# SmartCitizen_DVK.net
KiCad netlist of a schematic drawn in EAGLE
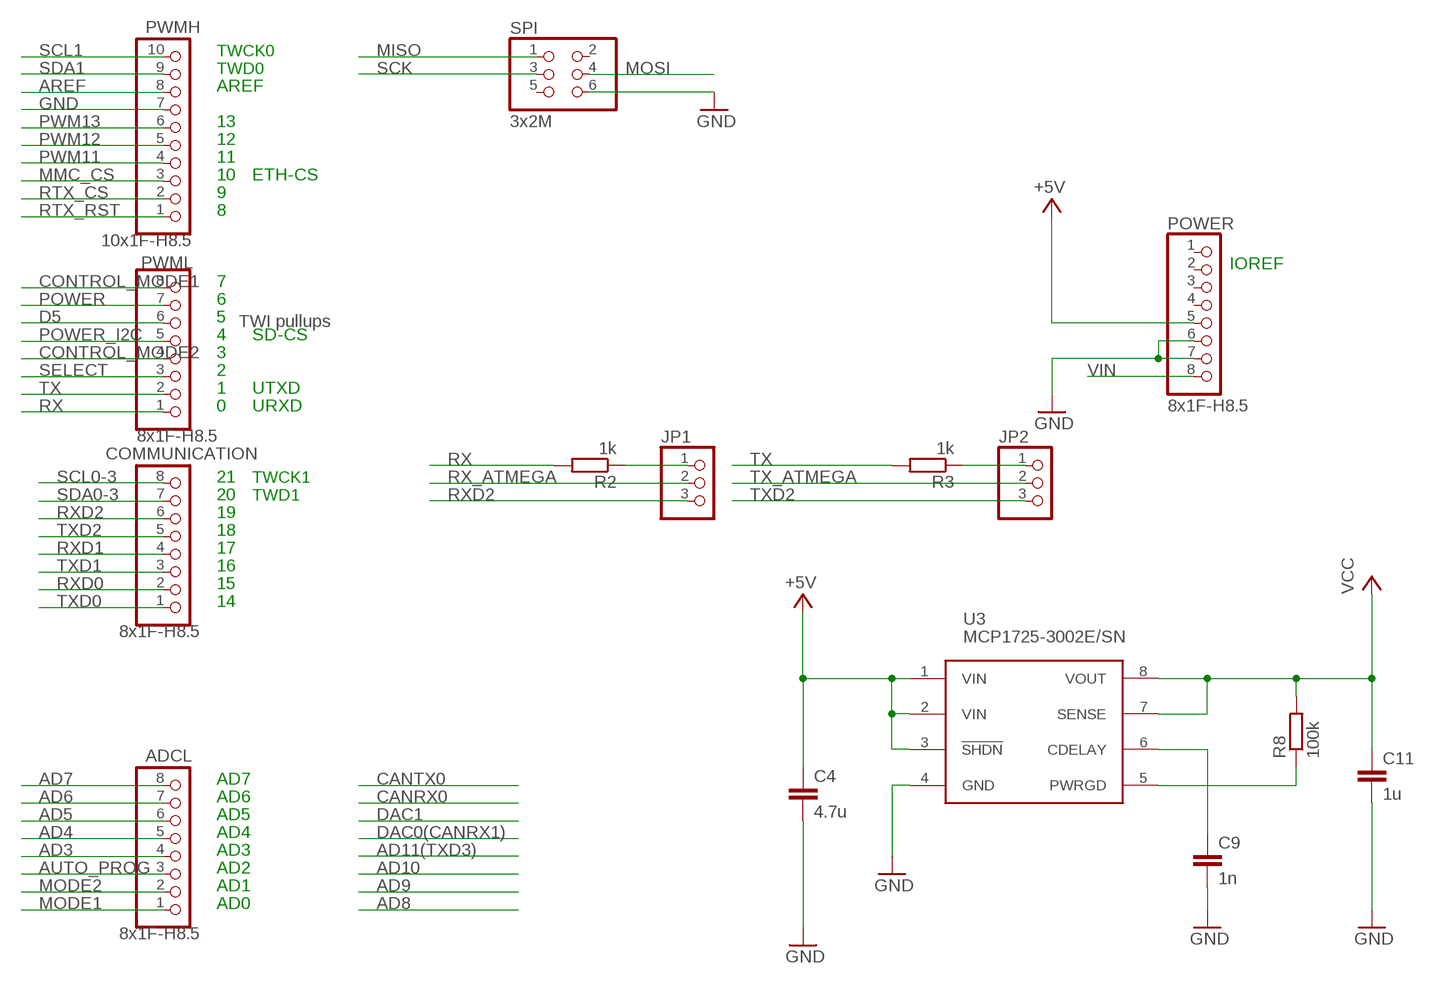
[diagram p0: schematic, sheet 1]
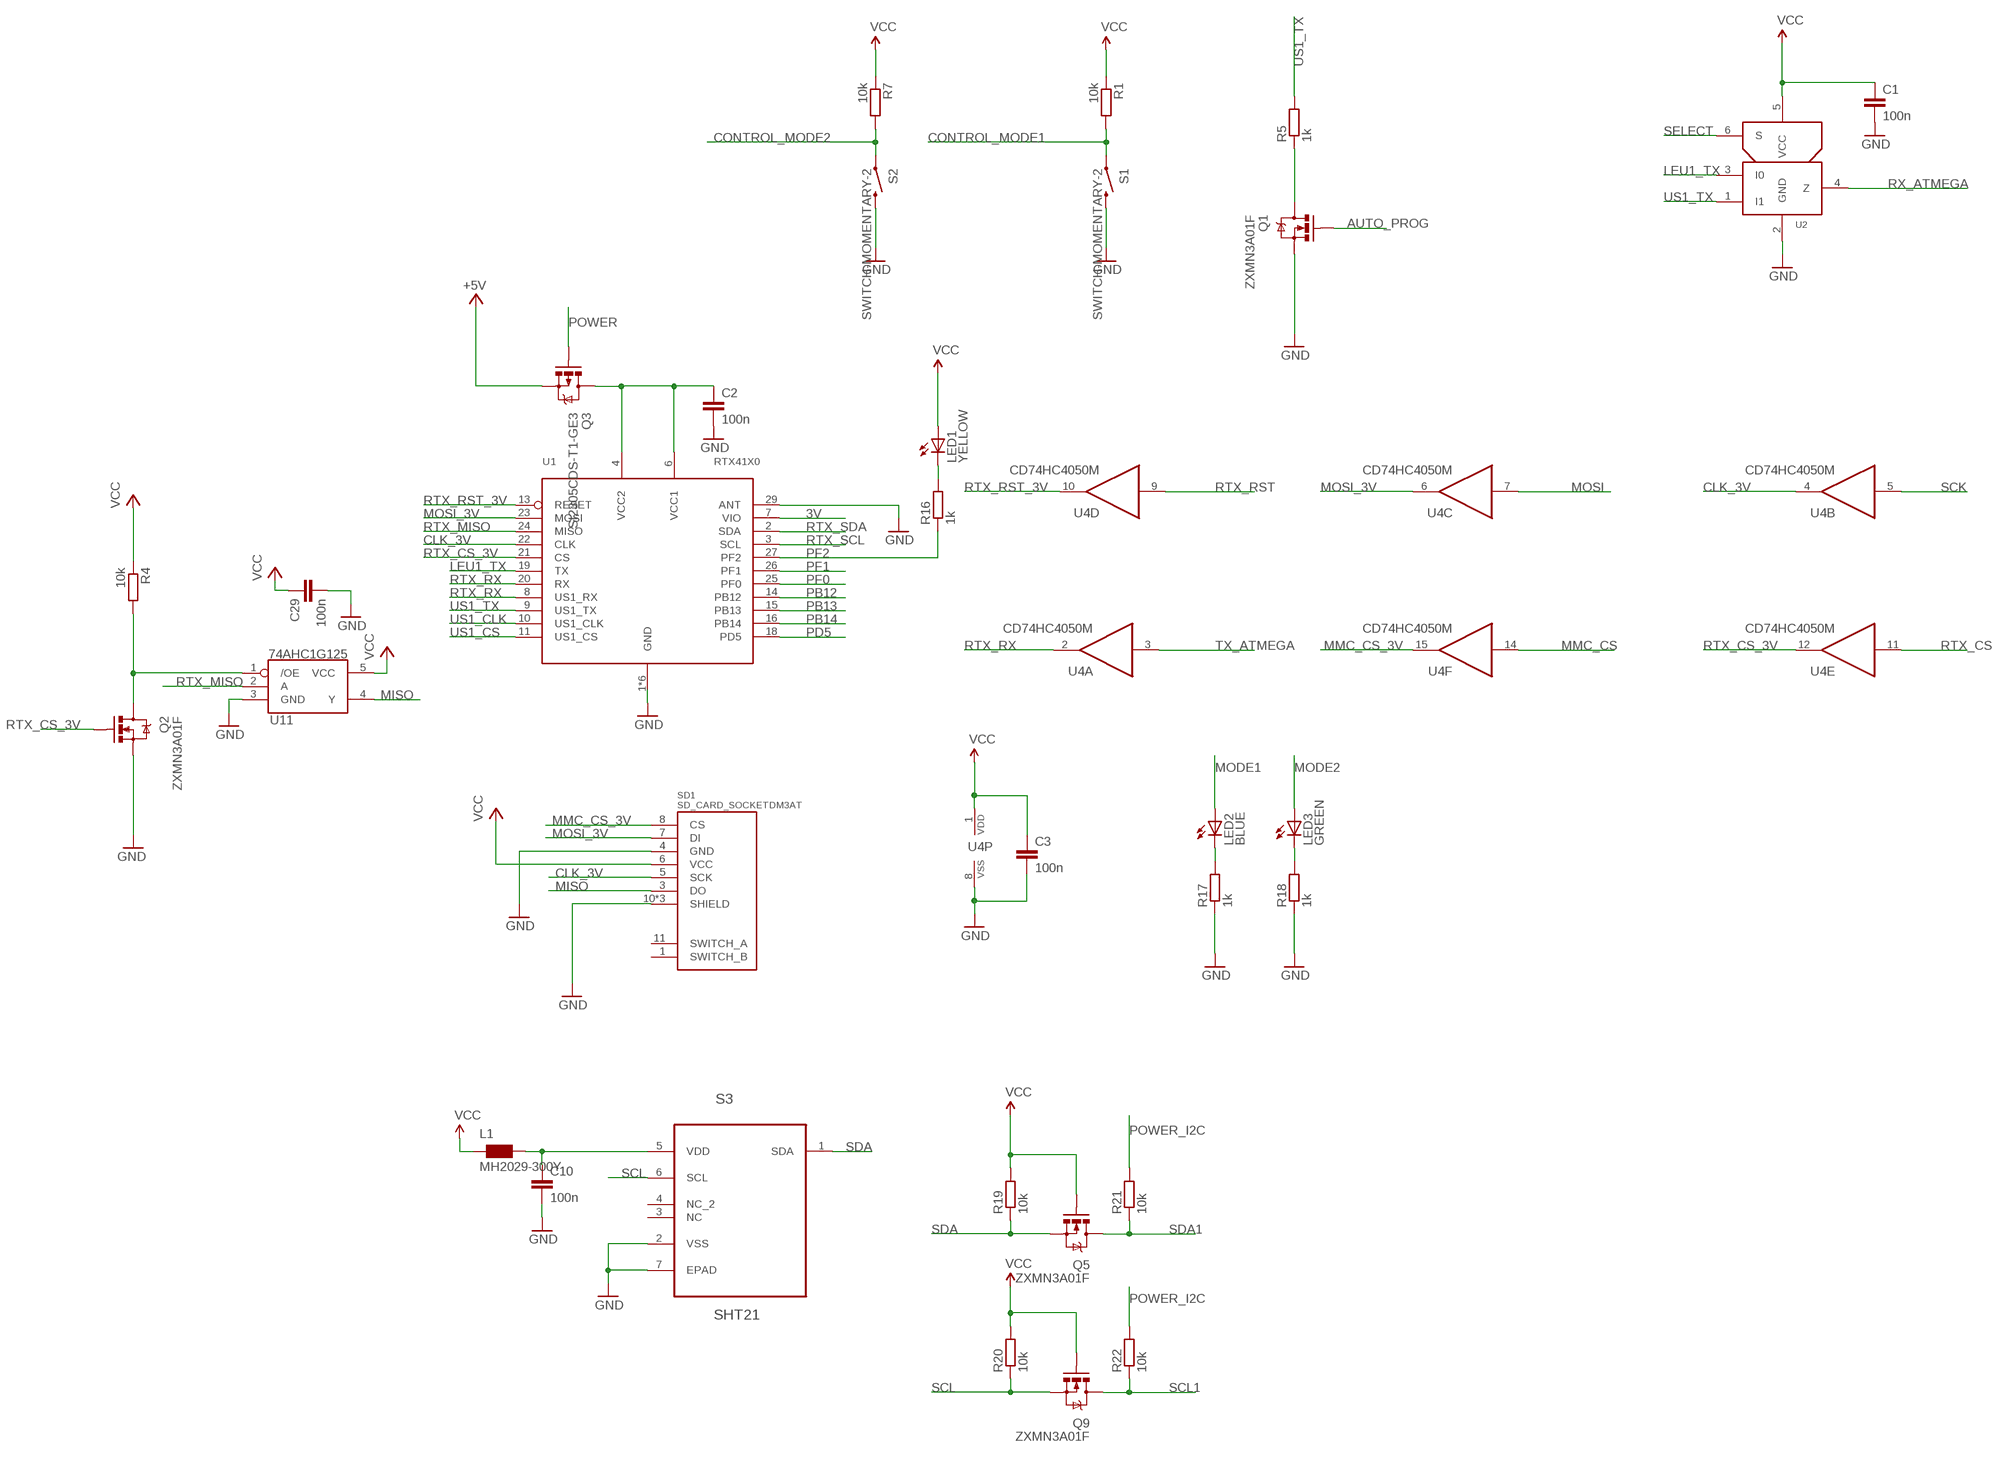
[diagram p1: schematic, sheet 2]

(export (version "E")
  (design (tool "Eeschema 10.0.6"))
  (components
    (comp (ref "C1")
      (value "100n")
      (footprint "eagle-import:C0805")
      (libsource (lib "eagle-import") (part "C-EUC0805"))
    )
    (comp (ref "C2")
      (value "100n")
      (footprint "eagle-import:C0805")
      (libsource (lib "eagle-import") (part "C-EUC0805"))
    )
    (comp (ref "C3")
      (value "100n")
      (footprint "eagle-import:C0805")
      (libsource (lib "eagle-import") (part "C-EUC0805"))
    )
    (comp (ref "C10")
      (value "100n")
      (footprint "eagle-import:C0805")
      (libsource (lib "eagle-import") (part "rcl_C-EUC0805"))
    )
    (comp (ref "C29")
      (value "100n")
      (footprint "eagle-import:C0805")
      (libsource (lib "eagle-import") (part "rcl_C-EUC0805"))
    )
    (comp (ref "L1")
      (value "MH2029-300Y")
      (footprint "eagle-import:0805")
      (libsource (lib "eagle-import") (part "WE-CBF_0805"))
    )
    (comp (ref "LED1")
      (value "YELLOW")
      (footprint "eagle-import:CHIPLED_0805")
      (libsource (lib "eagle-import") (part "LEDCHIPLED_0805"))
    )
    (comp (ref "LED2")
      (value "BLUE")
      (footprint "eagle-import:CHIPLED_0805")
      (libsource (lib "eagle-import") (part "LEDCHIPLED_0805"))
    )
    (comp (ref "LED3")
      (value "GREEN")
      (footprint "eagle-import:CHIPLED_0805")
      (libsource (lib "eagle-import") (part "LEDCHIPLED_0805"))
    )
    (comp (ref "Q1")
      (value "ZXMN3A01F")
      (footprint "eagle-import:SOT23")
      (libsource (lib "eagle-import") (part "MOSFET-NCHANNELBSS123LT1G"))
    )
    (comp (ref "Q2")
      (value "ZXMN3A01F")
      (footprint "eagle-import:SOT23")
      (libsource (lib "eagle-import") (part "MOSFET-NCHANNELBSS123LT1G"))
    )
    (comp (ref "Q3")
      (value "SI2305CDS-T1-GE3")
      (footprint "eagle-import:SOT23-3")
      (libsource (lib "eagle-import") (part "MOSFET-PCHANNEL"))
    )
    (comp (ref "Q5")
      (value "ZXMN3A01F")
      (footprint "eagle-import:SOT23")
      (libsource (lib "eagle-import") (part "MOSFET-NCHANNELBSS123LT1G"))
    )
    (comp (ref "Q9")
      (value "ZXMN3A01F")
      (footprint "eagle-import:SOT23")
      (libsource (lib "eagle-import") (part "MOSFET-NCHANNELBSS123LT1G"))
    )
    (comp (ref "R1")
      (value "10k")
      (footprint "eagle-import:R0805")
      (libsource (lib "eagle-import") (part "R-EU_R0805"))
    )
    (comp (ref "R4")
      (value "10k")
      (footprint "eagle-import:R0805")
      (libsource (lib "eagle-import") (part "R-EU_R0805"))
    )
    (comp (ref "R5")
      (value "1k")
      (footprint "eagle-import:R0805")
      (libsource (lib "eagle-import") (part "R-EU_R0805"))
    )
    (comp (ref "R7")
      (value "10k")
      (footprint "eagle-import:R0805")
      (libsource (lib "eagle-import") (part "R-EU_R0805"))
    )
    (comp (ref "R16")
      (value "1k")
      (footprint "eagle-import:R0805")
      (libsource (lib "eagle-import") (part "R-EU_R0805"))
    )
    (comp (ref "R17")
      (value "1k")
      (footprint "eagle-import:R0805")
      (libsource (lib "eagle-import") (part "R-EU_R0805"))
    )
    (comp (ref "R18")
      (value "1k")
      (footprint "eagle-import:R0805")
      (libsource (lib "eagle-import") (part "R-EU_R0805"))
    )
    (comp (ref "R19")
      (value "10k")
      (footprint "eagle-import:R0805")
      (libsource (lib "eagle-import") (part "R-EU_R0805"))
    )
    (comp (ref "R20")
      (value "10k")
      (footprint "eagle-import:R0805")
      (libsource (lib "eagle-import") (part "R-EU_R0805"))
    )
    (comp (ref "R21")
      (value "10k")
      (footprint "eagle-import:R0805")
      (libsource (lib "eagle-import") (part "R-EU_R0805"))
    )
    (comp (ref "R22")
      (value "10k")
      (footprint "eagle-import:R0805")
      (libsource (lib "eagle-import") (part "R-EU_R0805"))
    )
    (comp (ref "S1")
      (value "SWITCH-MOMENTARY-2")
      (footprint "eagle-import:TACTILE_SWITCH_TALL")
      (libsource (lib "eagle-import") (part "SWITCH-MOMENTARY-2"))
    )
    (comp (ref "S2")
      (value "SWITCH-MOMENTARY-2")
      (footprint "eagle-import:TACTILE_SWITCH_TALL")
      (libsource (lib "eagle-import") (part "SWITCH-MOMENTARY-2"))
    )
    (comp (ref "S3")
      (value "SHT21")
      (footprint "eagle-import:DFN300X300X110-7N")
      (libsource (lib "eagle-import") (part "SHT21"))
    )
    (comp (ref "SD1")
      (value "SD_CARD_SOCKETDM3AT")
      (footprint "eagle-import:DM3AT")
      (libsource (lib "eagle-import") (part "SD_CARD_SOCKETDM3AT"))
    )
    (comp (ref "U1")
      (value "RTX41X0")
      (footprint "eagle-import:RTX41X0")
      (libsource (lib "eagle-import") (part "RTX41X0"))
    )
    (comp (ref "U2")
      (value "NC7SZ157P6X")
      (footprint "eagle-import:SC70")
      (libsource (lib "eagle-import") (part "NC7SV157"))
    )
    (comp (ref "U4")
      (value "CD74HC4050M")
      (footprint "eagle-import:SO16")
      (libsource (lib "eagle-import") (part "4050D"))
    )
    (comp (ref "U11")
      (value "74AHC1G125")
      (footprint "eagle-import:SOT23-5")
      (libsource (lib "eagle-import") (part "74AHC1G125"))
    )
    (comp (ref "ADCL")
      (value "8x1F-H8.5")
      (footprint "eagle-import:1X08")
      (libsource (lib "eagle-import") (part "PINHD-1X8"))
    )
    (comp (ref "C4")
      (value "4.7u")
      (footprint "eagle-import:C0805")
      (libsource (lib "eagle-import") (part "rcl_C-EUC0805"))
    )
    (comp (ref "C9")
      (value "1n")
      (footprint "eagle-import:C0805")
      (libsource (lib "eagle-import") (part "rcl_C-EUC0805"))
    )
    (comp (ref "C11")
      (value "1u")
      (footprint "eagle-import:C0805")
      (libsource (lib "eagle-import") (part "rcl_C-EUC0805"))
    )
    (comp (ref "COMMUNICATION")
      (value "8x1F-H8.5")
      (footprint "eagle-import:1X08")
      (libsource (lib "eagle-import") (part "PINHD-1X8"))
    )
    (comp (ref "JP1")
      (value "PINHD-1X3")
      (footprint "eagle-import:1X03")
      (libsource (lib "eagle-import") (part "PINHD-1X3"))
    )
    (comp (ref "JP2")
      (value "PINHD-1X3")
      (footprint "eagle-import:1X03")
      (libsource (lib "eagle-import") (part "PINHD-1X3"))
    )
    (comp (ref "POWER")
      (value "8x1F-H8.5")
      (footprint "eagle-import:1X08")
      (libsource (lib "eagle-import") (part "PINHD-1X8"))
    )
    (comp (ref "PWMH")
      (value "10x1F-H8.5")
      (footprint "eagle-import:1X10")
      (libsource (lib "eagle-import") (part "PINHD-1X10"))
    )
    (comp (ref "PWML")
      (value "8x1F-H8.5")
      (footprint "eagle-import:1X08")
      (libsource (lib "eagle-import") (part "PINHD-1X8"))
    )
    (comp (ref "R2")
      (value "1k")
      (footprint "eagle-import:R0805")
      (libsource (lib "eagle-import") (part "R-EU_R0805"))
    )
    (comp (ref "R3")
      (value "1k")
      (footprint "eagle-import:R0805")
      (libsource (lib "eagle-import") (part "R-EU_R0805"))
    )
    (comp (ref "R8")
      (value "100k")
      (footprint "eagle-import:R0805")
      (libsource (lib "eagle-import") (part "R-EU_R0805"))
    )
    (comp (ref "SPI")
      (value "3x2M")
      (footprint "eagle-import:2X03")
      (libsource (lib "eagle-import") (part "PINHD-2X3"))
    )
    (comp (ref "U3")
      (value "MCP1725-3002E/SN")
      (footprint "eagle-import:SOIC8")
      (libsource (lib "eagle-import") (part "MCP1725"))
    )
  )
  (nets
    (net (code "1") (name "+5V") (class "Default")
      (node (ref "C4") (pin "1") (pinfunction "1_1") (pintype "passive"))
      (node (ref "POWER") (pin "5") (pinfunction "5_5") (pintype "passive"))
      (node (ref "Q3") (pin "2") (pinfunction "S_2") (pintype "passive"))
      (node (ref "U3") (pin "1") (pinfunction "VIN_1") (pintype "bidirectional"))
      (node (ref "U3") (pin "2") (pinfunction "VIN_2") (pintype "bidirectional"))
      (node (ref "U3") (pin "3") (pinfunction "~{SHDN}_3") (pintype "bidirectional"))
    )
    (net (code "2") (name "3V") (class "Default")
      (node (ref "U1") (pin "7") (pinfunction "VIO_7") (pintype "bidirectional"))
    )
    (net (code "3") (name "AD3") (class "Default")
      (node (ref "ADCL") (pin "4") (pinfunction "4_4") (pintype "passive"))
    )
    (net (code "4") (name "AD4") (class "Default")
      (node (ref "ADCL") (pin "5") (pinfunction "5_5") (pintype "passive"))
    )
    (net (code "5") (name "AD5") (class "Default")
      (node (ref "ADCL") (pin "6") (pinfunction "6_6") (pintype "passive"))
    )
    (net (code "6") (name "AD6") (class "Default")
      (node (ref "ADCL") (pin "7") (pinfunction "7_7") (pintype "passive"))
    )
    (net (code "7") (name "AD7") (class "Default")
      (node (ref "ADCL") (pin "8") (pinfunction "8_8") (pintype "passive"))
    )
    (net (code "12") (name "AREF") (class "Default")
      (node (ref "PWMH") (pin "8") (pinfunction "8_8") (pintype "passive"))
    )
    (net (code "13") (name "AUTO_PROG") (class "Default")
      (node (ref "ADCL") (pin "3") (pinfunction "3_3") (pintype "passive"))
      (node (ref "Q1") (pin "1") (pinfunction "G_1") (pintype "passive"))
    )
    (net (code "16") (name "CLK_3V") (class "Default")
      (node (ref "SD1") (pin "5") (pinfunction "SCK_5") (pintype "bidirectional"))
      (node (ref "U1") (pin "22") (pinfunction "CLK_22") (pintype "bidirectional"))
      (node (ref "U4") (pin "4") (pinfunction "O_4") (pintype "output"))
    )
    (net (code "17") (name "CONTROL_MODE1") (class "Default")
      (node (ref "PWML") (pin "8") (pinfunction "8_8") (pintype "passive"))
      (node (ref "R1") (pin "2") (pinfunction "2_2") (pintype "passive"))
      (node (ref "S1") (pin "A2") (pinfunction "1_A2") (pintype "passive"))
    )
    (net (code "18") (name "CONTROL_MODE2") (class "Default")
      (node (ref "PWML") (pin "4") (pinfunction "4_4") (pintype "passive"))
      (node (ref "R7") (pin "2") (pinfunction "2_2") (pintype "passive"))
      (node (ref "S2") (pin "A2") (pinfunction "1_A2") (pintype "passive"))
    )
    (net (code "19") (name "D5") (class "Default")
      (node (ref "PWML") (pin "6") (pinfunction "6_6") (pintype "passive"))
    )
    (net (code "22") (name "GND") (class "Default")
      (node (ref "C1") (pin "2") (pinfunction "2_2") (pintype "passive"))
      (node (ref "C10") (pin "2") (pinfunction "2_2") (pintype "passive"))
      (node (ref "C11") (pin "2") (pinfunction "2_2") (pintype "passive"))
      (node (ref "C2") (pin "2") (pinfunction "2_2") (pintype "passive"))
      (node (ref "C29") (pin "2") (pinfunction "2_2") (pintype "passive"))
      (node (ref "C3") (pin "2") (pinfunction "2_2") (pintype "passive"))
      (node (ref "C4") (pin "2") (pinfunction "2_2") (pintype "passive"))
      (node (ref "C9") (pin "2") (pinfunction "2_2") (pintype "passive"))
      (node (ref "POWER") (pin "6") (pinfunction "6_6") (pintype "passive"))
      (node (ref "POWER") (pin "7") (pinfunction "7_7") (pintype "passive"))
      (node (ref "PWMH") (pin "7") (pinfunction "7_7") (pintype "passive"))
      (node (ref "Q1") (pin "2") (pinfunction "S_2") (pintype "passive"))
      (node (ref "Q2") (pin "2") (pinfunction "S_2") (pintype "passive"))
      (node (ref "R17") (pin "1") (pinfunction "1_1") (pintype "passive"))
      (node (ref "R18") (pin "1") (pinfunction "1_1") (pintype "passive"))
      (node (ref "S1") (pin "B2") (pinfunction "2_B2") (pintype "passive"))
      (node (ref "S2") (pin "B2") (pinfunction "2_B2") (pintype "passive"))
      (node (ref "S3") (pin "2") (pinfunction "VSS_2") (pintype "power_in"))
      (node (ref "S3") (pin "7") (pinfunction "EPAD_7") (pintype "passive"))
      (node (ref "SD1") (pin "10") (pinfunction "SHIELD_10") (pintype "bidirectional"))
      (node (ref "SD1") (pin "12") (pinfunction "SHIELD_12") (pintype "bidirectional"))
      (node (ref "SD1") (pin "13") (pinfunction "SHIELD_13") (pintype "bidirectional"))
      (node (ref "SD1") (pin "4") (pinfunction "GND_4") (pintype "bidirectional"))
      (node (ref "SPI") (pin "6") (pinfunction "6_6") (pintype "passive"))
      (node (ref "U1") (pin "1") (pinfunction "GND_1") (pintype "power_in"))
      (node (ref "U1") (pin "12") (pinfunction "GND_12") (pintype "power_in"))
      (node (ref "U1") (pin "17") (pinfunction "GND_17") (pintype "power_in"))
      (node (ref "U1") (pin "28") (pinfunction "GND_28") (pintype "power_in"))
      (node (ref "U1") (pin "29") (pinfunction "ANT_29") (pintype "bidirectional"))
      (node (ref "U1") (pin "30") (pinfunction "GND_30") (pintype "power_in"))
      (node (ref "U1") (pin "5") (pinfunction "GND_5") (pintype "power_in"))
      (node (ref "U11") (pin "3") (pinfunction "GND_3") (pintype "bidirectional"))
      (node (ref "U2") (pin "2") (pinfunction "GND_2") (pintype "bidirectional"))
      (node (ref "U3") (pin "4") (pinfunction "GND_4") (pintype "bidirectional"))
      (node (ref "U4") (pin "8") (pinfunction "VSS_8") (pintype "power_in"))
    )
    (net (code "23") (name "LEU1_TX") (class "Default")
      (node (ref "U1") (pin "19") (pinfunction "TX_19") (pintype "bidirectional"))
      (node (ref "U2") (pin "3") (pinfunction "I0_3") (pintype "bidirectional"))
    )
    (net (code "24") (name "MISO") (class "Default")
      (node (ref "SD1") (pin "3") (pinfunction "DO_3") (pintype "bidirectional"))
      (node (ref "SPI") (pin "1") (pinfunction "1_1") (pintype "passive"))
      (node (ref "U11") (pin "4") (pinfunction "Y_4") (pintype "bidirectional"))
    )
    (net (code "25") (name "MMC_CS") (class "Default")
      (node (ref "PWMH") (pin "3") (pinfunction "3_3") (pintype "passive"))
      (node (ref "U4") (pin "14") (pinfunction "I_14") (pintype "input"))
    )
    (net (code "26") (name "MMC_CS_3V") (class "Default")
      (node (ref "SD1") (pin "8") (pinfunction "CS_8") (pintype "bidirectional"))
      (node (ref "U4") (pin "15") (pinfunction "O_15") (pintype "output"))
    )
    (net (code "27") (name "MODE1") (class "Default")
      (node (ref "ADCL") (pin "1") (pinfunction "1_1") (pintype "passive"))
      (node (ref "LED2") (pin "A") (pinfunction "A_A") (pintype "passive"))
    )
    (net (code "28") (name "MODE2") (class "Default")
      (node (ref "ADCL") (pin "2") (pinfunction "2_2") (pintype "passive"))
      (node (ref "LED3") (pin "A") (pinfunction "A_A") (pintype "passive"))
    )
    (net (code "29") (name "MOSI") (class "Default")
      (node (ref "SPI") (pin "4") (pinfunction "4_4") (pintype "passive"))
      (node (ref "U4") (pin "7") (pinfunction "I_7") (pintype "input"))
    )
    (net (code "30") (name "MOSI_3V") (class "Default")
      (node (ref "SD1") (pin "7") (pinfunction "DI_7") (pintype "bidirectional"))
      (node (ref "U1") (pin "23") (pinfunction "MOSI_23") (pintype "bidirectional"))
      (node (ref "U4") (pin "6") (pinfunction "O_6") (pintype "output"))
    )
    (net (code "31") (name "Net-(JP1-Pad1)") (class "Default")
      (node (ref "JP1") (pin "1") (pinfunction "1_1") (pintype "passive"))
      (node (ref "R2") (pin "1") (pinfunction "1_1") (pintype "passive"))
    )
    (net (code "32") (name "Net-(JP2-Pad1)") (class "Default")
      (node (ref "JP2") (pin "1") (pinfunction "1_1") (pintype "passive"))
      (node (ref "R3") (pin "1") (pinfunction "1_1") (pintype "passive"))
    )
    (net (code "33") (name "Net-(LED1-PadC)") (class "Default")
      (node (ref "LED1") (pin "C") (pinfunction "C_C") (pintype "passive"))
      (node (ref "R16") (pin "2") (pinfunction "2_2") (pintype "passive"))
    )
    (net (code "34") (name "Net-(LED2-PadC)") (class "Default")
      (node (ref "LED2") (pin "C") (pinfunction "C_C") (pintype "passive"))
      (node (ref "R17") (pin "2") (pinfunction "2_2") (pintype "passive"))
    )
    (net (code "35") (name "Net-(LED3-PadC)") (class "Default")
      (node (ref "LED3") (pin "C") (pinfunction "C_C") (pintype "passive"))
      (node (ref "R18") (pin "2") (pinfunction "2_2") (pintype "passive"))
    )
    (net (code "36") (name "Net-(Q1-D)") (class "Default")
      (node (ref "Q1") (pin "3") (pinfunction "D_3") (pintype "passive"))
      (node (ref "R5") (pin "1") (pinfunction "1_1") (pintype "passive"))
    )
    (net (code "37") (name "Net-(Q2-D)") (class "Default")
      (node (ref "Q2") (pin "3") (pinfunction "D_3") (pintype "passive"))
      (node (ref "R4") (pin "2") (pinfunction "2_2") (pintype "passive"))
      (node (ref "U11") (pin "1") (pinfunction "/OE_1") (pintype "bidirectional"))
    )
    (net (code "38") (name "Net-(Q3-D)") (class "Default")
      (node (ref "C2") (pin "1") (pinfunction "1_1") (pintype "passive"))
      (node (ref "Q3") (pin "3") (pinfunction "D_3") (pintype "passive"))
      (node (ref "U1") (pin "4") (pinfunction "VCC2_4") (pintype "power_in"))
      (node (ref "U1") (pin "6") (pinfunction "VCC1_6") (pintype "power_in"))
    )
    (net (code "39") (name "Net-(S3-VDD)") (class "Default")
      (node (ref "C10") (pin "1") (pinfunction "1_1") (pintype "passive"))
      (node (ref "L1") (pin "2") (pinfunction "2_2") (pintype "passive"))
      (node (ref "S3") (pin "5") (pinfunction "VDD_5") (pintype "power_in"))
    )
    (net (code "40") (name "Net-(U3-CDELAY)") (class "Default")
      (node (ref "C9") (pin "1") (pinfunction "1_1") (pintype "passive"))
      (node (ref "U3") (pin "6") (pinfunction "CDELAY_6") (pintype "bidirectional"))
    )
    (net (code "41") (name "Net-(U3-PWRGD)") (class "Default")
      (node (ref "R8") (pin "1") (pinfunction "1_1") (pintype "passive"))
      (node (ref "U3") (pin "5") (pinfunction "PWRGD_5") (pintype "bidirectional"))
    )
    (net (code "42") (name "PB12") (class "Default")
      (node (ref "U1") (pin "14") (pinfunction "PB12_14") (pintype "bidirectional"))
    )
    (net (code "43") (name "PB13") (class "Default")
      (node (ref "U1") (pin "15") (pinfunction "PB13_15") (pintype "bidirectional"))
    )
    (net (code "44") (name "PB14") (class "Default")
      (node (ref "U1") (pin "16") (pinfunction "PB14_16") (pintype "bidirectional"))
    )
    (net (code "45") (name "PD5") (class "Default")
      (node (ref "U1") (pin "18") (pinfunction "PD5_18") (pintype "bidirectional"))
    )
    (net (code "46") (name "PF0") (class "Default")
      (node (ref "U1") (pin "25") (pinfunction "PF0_25") (pintype "bidirectional"))
    )
    (net (code "47") (name "PF1") (class "Default")
      (node (ref "U1") (pin "26") (pinfunction "PF1_26") (pintype "bidirectional"))
    )
    (net (code "48") (name "PF2") (class "Default")
      (node (ref "R16") (pin "1") (pinfunction "1_1") (pintype "passive"))
      (node (ref "U1") (pin "27") (pinfunction "PF2_27") (pintype "bidirectional"))
    )
    (net (code "49") (name "POWER") (class "Default")
      (node (ref "PWML") (pin "7") (pinfunction "7_7") (pintype "passive"))
      (node (ref "Q3") (pin "1") (pinfunction "G_1") (pintype "passive"))
    )
    (net (code "50") (name "POWER_I2C") (class "Default")
      (node (ref "PWML") (pin "5") (pinfunction "5_5") (pintype "passive"))
      (node (ref "R21") (pin "2") (pinfunction "2_2") (pintype "passive"))
      (node (ref "R22") (pin "2") (pinfunction "2_2") (pintype "passive"))
    )
    (net (code "51") (name "PWM11") (class "Default")
      (node (ref "PWMH") (pin "4") (pinfunction "4_4") (pintype "passive"))
    )
    (net (code "52") (name "PWM12") (class "Default")
      (node (ref "PWMH") (pin "5") (pinfunction "5_5") (pintype "passive"))
    )
    (net (code "53") (name "PWM13") (class "Default")
      (node (ref "PWMH") (pin "6") (pinfunction "6_6") (pintype "passive"))
    )
    (net (code "54") (name "RTX_CS") (class "Default")
      (node (ref "PWMH") (pin "2") (pinfunction "2_2") (pintype "passive"))
      (node (ref "U4") (pin "11") (pinfunction "I_11") (pintype "input"))
    )
    (net (code "55") (name "RTX_CS_3V") (class "Default")
      (node (ref "Q2") (pin "1") (pinfunction "G_1") (pintype "passive"))
      (node (ref "U1") (pin "21") (pinfunction "CS_21") (pintype "input"))
      (node (ref "U4") (pin "12") (pinfunction "O_12") (pintype "output"))
    )
    (net (code "56") (name "RTX_MISO") (class "Default")
      (node (ref "U1") (pin "24") (pinfunction "MISO_24") (pintype "bidirectional"))
      (node (ref "U11") (pin "2") (pinfunction "A_2") (pintype "bidirectional"))
    )
    (net (code "57") (name "RTX_RST") (class "Default")
      (node (ref "PWMH") (pin "1") (pinfunction "1_1") (pintype "passive"))
      (node (ref "U4") (pin "9") (pinfunction "I_9") (pintype "input"))
    )
    (net (code "58") (name "RTX_RST_3V") (class "Default")
      (node (ref "U1") (pin "13") (pinfunction "RESET_13") (pintype "bidirectional"))
      (node (ref "U4") (pin "10") (pinfunction "O_10") (pintype "output"))
    )
    (net (code "59") (name "RTX_RX") (class "Default")
      (node (ref "U1") (pin "20") (pinfunction "RX_20") (pintype "input"))
      (node (ref "U1") (pin "8") (pinfunction "US1_RX_8") (pintype "input"))
      (node (ref "U4") (pin "2") (pinfunction "O_2") (pintype "output"))
    )
    (net (code "60") (name "RTX_SCL") (class "Default")
      (node (ref "U1") (pin "3") (pinfunction "SCL_3") (pintype "bidirectional"))
    )
    (net (code "61") (name "RTX_SDA") (class "Default")
      (node (ref "U1") (pin "2") (pinfunction "SDA_2") (pintype "bidirectional"))
    )
    (net (code "62") (name "RX") (class "Default")
      (node (ref "PWML") (pin "1") (pinfunction "1_1") (pintype "passive"))
      (node (ref "R2") (pin "2") (pinfunction "2_2") (pintype "passive"))
    )
    (net (code "63") (name "RXD0") (class "Default")
      (node (ref "COMMUNICATION") (pin "2") (pinfunction "2_2") (pintype "passive"))
    )
    (net (code "64") (name "RXD1") (class "Default")
      (node (ref "COMMUNICATION") (pin "4") (pinfunction "4_4") (pintype "passive"))
    )
    (net (code "65") (name "RXD2") (class "Default")
      (node (ref "COMMUNICATION") (pin "6") (pinfunction "6_6") (pintype "passive"))
      (node (ref "JP1") (pin "3") (pinfunction "3_3") (pintype "passive"))
    )
    (net (code "66") (name "RX_ATMEGA") (class "Default")
      (node (ref "JP1") (pin "2") (pinfunction "2_2") (pintype "passive"))
      (node (ref "U2") (pin "4") (pinfunction "Z_4") (pintype "bidirectional"))
    )
    (net (code "67") (name "SCK") (class "Default")
      (node (ref "SPI") (pin "3") (pinfunction "3_3") (pintype "passive"))
      (node (ref "U4") (pin "5") (pinfunction "I_5") (pintype "input"))
    )
    (net (code "68") (name "SCL") (class "Default")
      (node (ref "Q9") (pin "2") (pinfunction "S_2") (pintype "passive"))
      (node (ref "R20") (pin "1") (pinfunction "1_1") (pintype "passive"))
      (node (ref "S3") (pin "6") (pinfunction "SCL_6") (pintype "input"))
    )
    (net (code "69") (name "SCL0-3") (class "Default")
      (node (ref "COMMUNICATION") (pin "8") (pinfunction "8_8") (pintype "passive"))
    )
    (net (code "70") (name "SCL1") (class "Default")
      (node (ref "PWMH") (pin "10") (pinfunction "10_10") (pintype "passive"))
      (node (ref "Q9") (pin "3") (pinfunction "D_3") (pintype "passive"))
      (node (ref "R22") (pin "1") (pinfunction "1_1") (pintype "passive"))
    )
    (net (code "71") (name "SDA") (class "Default")
      (node (ref "Q5") (pin "2") (pinfunction "S_2") (pintype "passive"))
      (node (ref "R19") (pin "1") (pinfunction "1_1") (pintype "passive"))
      (node (ref "S3") (pin "1") (pinfunction "SDA_1") (pintype "bidirectional"))
    )
    (net (code "72") (name "SDA0-3") (class "Default")
      (node (ref "COMMUNICATION") (pin "7") (pinfunction "7_7") (pintype "passive"))
    )
    (net (code "73") (name "SDA1") (class "Default")
      (node (ref "PWMH") (pin "9") (pinfunction "9_9") (pintype "passive"))
      (node (ref "Q5") (pin "3") (pinfunction "D_3") (pintype "passive"))
      (node (ref "R21") (pin "1") (pinfunction "1_1") (pintype "passive"))
    )
    (net (code "74") (name "SELECT") (class "Default")
      (node (ref "PWML") (pin "3") (pinfunction "3_3") (pintype "passive"))
      (node (ref "U2") (pin "6") (pinfunction "S_6") (pintype "bidirectional"))
    )
    (net (code "75") (name "TX") (class "Default")
      (node (ref "PWML") (pin "2") (pinfunction "2_2") (pintype "passive"))
      (node (ref "R3") (pin "2") (pinfunction "2_2") (pintype "passive"))
    )
    (net (code "76") (name "TXD0") (class "Default")
      (node (ref "COMMUNICATION") (pin "1") (pinfunction "1_1") (pintype "passive"))
    )
    (net (code "77") (name "TXD1") (class "Default")
      (node (ref "COMMUNICATION") (pin "3") (pinfunction "3_3") (pintype "passive"))
    )
    (net (code "78") (name "TXD2") (class "Default")
      (node (ref "COMMUNICATION") (pin "5") (pinfunction "5_5") (pintype "passive"))
      (node (ref "JP2") (pin "3") (pinfunction "3_3") (pintype "passive"))
    )
    (net (code "79") (name "TX_ATMEGA") (class "Default")
      (node (ref "JP2") (pin "2") (pinfunction "2_2") (pintype "passive"))
      (node (ref "U4") (pin "3") (pinfunction "I_3") (pintype "input"))
    )
    (net (code "80") (name "US1_CLK") (class "Default")
      (node (ref "U1") (pin "10") (pinfunction "US1_CLK_10") (pintype "bidirectional"))
    )
    (net (code "81") (name "US1_CS") (class "Default")
      (node (ref "U1") (pin "11") (pinfunction "US1_CS_11") (pintype "input"))
    )
    (net (code "82") (name "US1_TX") (class "Default")
      (node (ref "R5") (pin "2") (pinfunction "2_2") (pintype "passive"))
      (node (ref "U1") (pin "9") (pinfunction "US1_TX_9") (pintype "bidirectional"))
      (node (ref "U2") (pin "1") (pinfunction "I1_1") (pintype "bidirectional"))
    )
    (net (code "83") (name "VCC") (class "Default")
      (node (ref "C1") (pin "1") (pinfunction "1_1") (pintype "passive"))
      (node (ref "C11") (pin "1") (pinfunction "1_1") (pintype "passive"))
      (node (ref "C29") (pin "1") (pinfunction "1_1") (pintype "passive"))
      (node (ref "C3") (pin "1") (pinfunction "1_1") (pintype "passive"))
      (node (ref "L1") (pin "1") (pinfunction "1_1") (pintype "passive"))
      (node (ref "LED1") (pin "A") (pinfunction "A_A") (pintype "passive"))
      (node (ref "Q5") (pin "1") (pinfunction "G_1") (pintype "passive"))
      (node (ref "Q9") (pin "1") (pinfunction "G_1") (pintype "passive"))
      (node (ref "R1") (pin "1") (pinfunction "1_1") (pintype "passive"))
      (node (ref "R19") (pin "2") (pinfunction "2_2") (pintype "passive"))
      (node (ref "R20") (pin "2") (pinfunction "2_2") (pintype "passive"))
      (node (ref "R4") (pin "1") (pinfunction "1_1") (pintype "passive"))
      (node (ref "R7") (pin "1") (pinfunction "1_1") (pintype "passive"))
      (node (ref "R8") (pin "2") (pinfunction "2_2") (pintype "passive"))
      (node (ref "SD1") (pin "6") (pinfunction "VCC_6") (pintype "bidirectional"))
      (node (ref "U11") (pin "5") (pinfunction "VCC_5") (pintype "bidirectional"))
      (node (ref "U2") (pin "5") (pinfunction "VCC_5") (pintype "bidirectional"))
      (node (ref "U3") (pin "7") (pinfunction "SENSE_7") (pintype "bidirectional"))
      (node (ref "U3") (pin "8") (pinfunction "VOUT_8") (pintype "bidirectional"))
      (node (ref "U4") (pin "1") (pinfunction "VDD_1") (pintype "power_in"))
    )
    (net (code "84") (name "VIN") (class "Default")
      (node (ref "POWER") (pin "8") (pinfunction "8_8") (pintype "passive"))
    )
    (net (code "85") (name "unconnected-(POWER-Pad1)") (class "Default")
      (node (ref "POWER") (pin "1") (pinfunction "1_1") (pintype "passive"))
    )
    (net (code "86") (name "unconnected-(POWER-Pad2)") (class "Default")
      (node (ref "POWER") (pin "2") (pinfunction "2_2") (pintype "passive"))
    )
    (net (code "87") (name "unconnected-(POWER-Pad3)") (class "Default")
      (node (ref "POWER") (pin "3") (pinfunction "3_3") (pintype "passive"))
    )
    (net (code "88") (name "unconnected-(POWER-Pad4)") (class "Default")
      (node (ref "POWER") (pin "4") (pinfunction "4_4") (pintype "passive"))
    )
    (net (code "89") (name "unconnected-(S3-NC-Pad3)") (class "Default")
      (node (ref "S3") (pin "3") (pinfunction "NC_3") (pintype "no_connect"))
    )
    (net (code "90") (name "unconnected-(S3-NC_2-Pad4)") (class "Default")
      (node (ref "S3") (pin "4") (pinfunction "NC_2_4") (pintype "no_connect"))
    )
    (net (code "91") (name "unconnected-(SD1-SWITCH_A-Pad11)") (class "Default")
      (node (ref "SD1") (pin "11") (pinfunction "SWITCH_A_11") (pintype "bidirectional"))
    )
    (net (code "92") (name "unconnected-(SD1-SWITCH_B-Pad1)") (class "Default")
      (node (ref "SD1") (pin "1") (pinfunction "SWITCH_B_1") (pintype "bidirectional"))
    )
    (net (code "93") (name "unconnected-(SPI-Pad2)") (class "Default")
      (node (ref "SPI") (pin "2") (pinfunction "2_2") (pintype "passive"))
    )
    (net (code "94") (name "unconnected-(SPI-Pad5)") (class "Default")
      (node (ref "SPI") (pin "5") (pinfunction "5_5") (pintype "passive"))
    )
  )
)
